# Communications_Module.net
KiCad netlist of a schematic drawn in Altium Designer
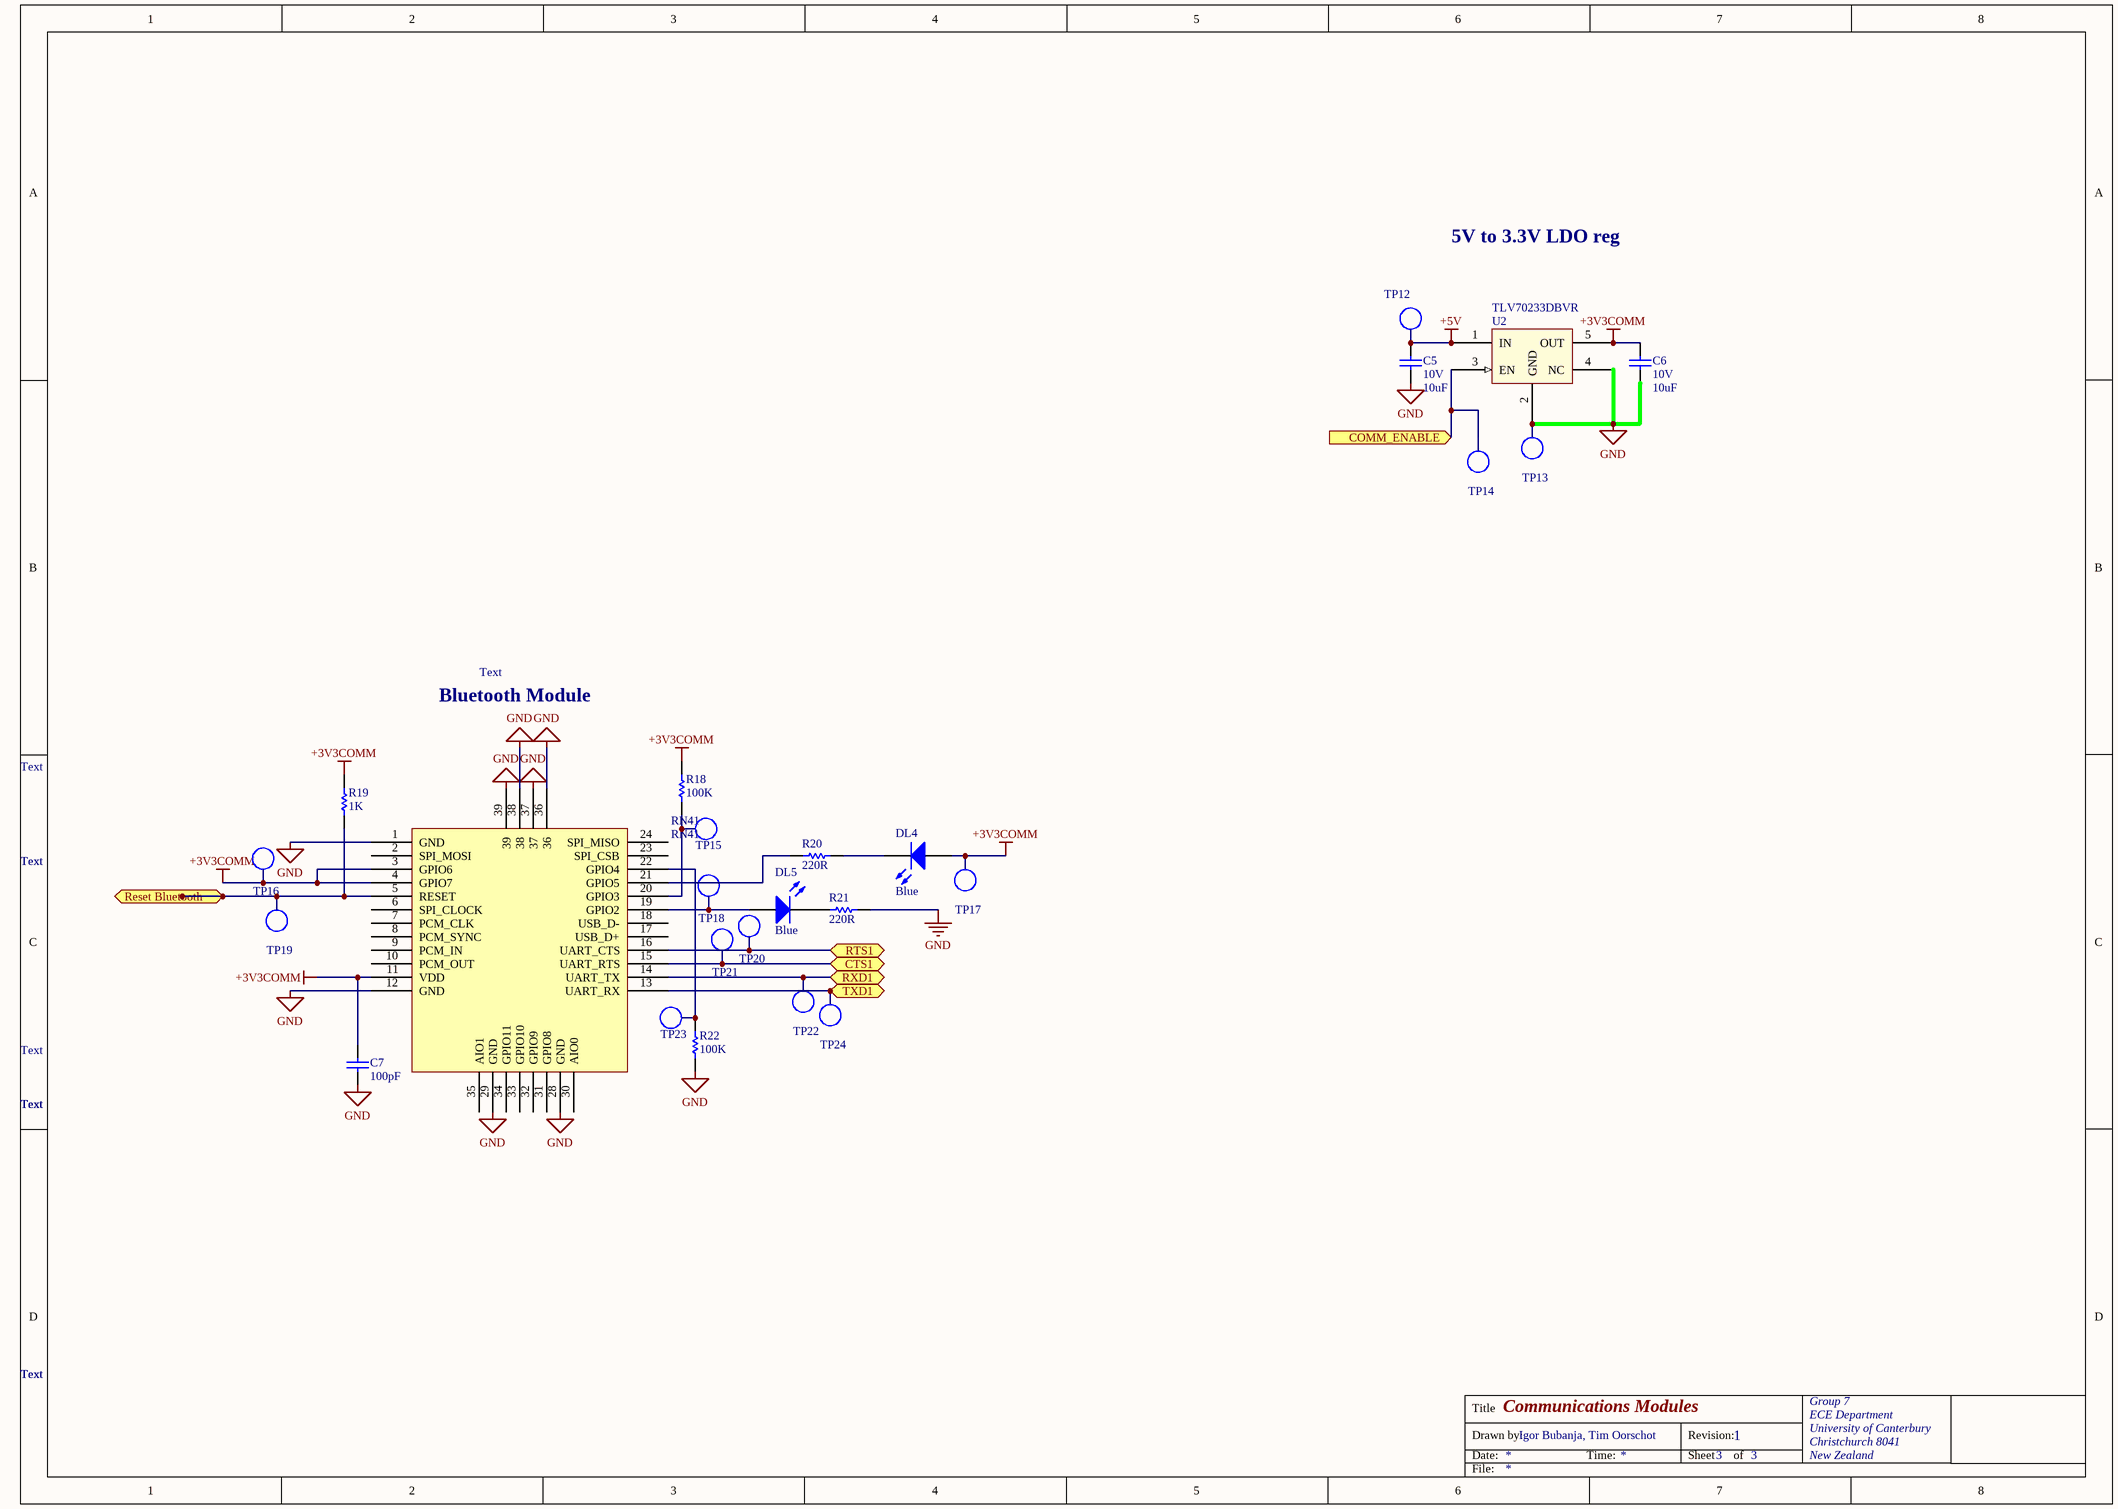
[diagram p0: Communications_Module.SchDoc]

(export (version "E")
  (design (tool "Eeschema 10.0.6"))
  (components
    (comp (ref "C5")
      (value "10uF")
      (footprint "CAPC1608L")
      (description "CAP CER 10UF X5R +-20% 10V 0603")
      (fields (field (name "VOLTAGE - RATED") "10V"))
      (libsource (lib "ECE Components_15_7") (part "CC_10uF_0603"))
    )
    (comp (ref "C6")
      (value "10uF")
      (footprint "CAPC1608L")
      (description "CAP CER 10UF X5R +-20% 10V 0603")
      (fields (field (name "VOLTAGE - RATED") "10V"))
      (libsource (lib "ECE Components_15_7") (part "CC_10uF_0603"))
    )
    (comp (ref "C7")
      (value "100pF")
      (footprint "CAPC1608L")
      (description "CAP CER 100pF NPO/COG +-5% 50V 0603")
      (libsource (lib "ECE Components_15_8") (part "CC_100pF_0603"))
    )
    (comp (ref "DL4")
      (value "Blue")
      (footprint "WL-SMCW0603")
      (description "LED Blue 270mcd 0603 SMD")
      (fields
        (field (name "MANUFACTURER") "WURTH ELEKTRONIK")
        (field (name "MANUFACTURER PART NUMBER") "150060BS75000")
        (field (name "LED COLOUR") "Blue")
      )
      (libsource (lib "ECE Components_15_8") (part "DL_150060BS75000"))
    )
    (comp (ref "DL5")
      (value "Blue")
      (footprint "WL-SMCW0603")
      (description "LED Blue 270mcd 0603 SMD")
      (fields
        (field (name "MANUFACTURER") "WURTH ELEKTRONIK")
        (field (name "MANUFACTURER PART NUMBER") "150060BS75000")
        (field (name "LED COLOUR") "Blue")
      )
      (libsource (lib "ECE Components_15_8") (part "DL_150060BS75000"))
    )
    (comp (ref "R18")
      (value "100K")
      (footprint "RESC1608L")
      (description "RES 100K OHM 1/10W 5% 0603 SMD")
      (libsource (lib "ECE Components_15_8") (part "RS_100K"))
    )
    (comp (ref "R19")
      (value "1K")
      (footprint "RESC1608L")
      (description "RES 1.0K OHM 1/10W 5% 0603 SMD")
      (libsource (lib "ECE Components_15_8") (part "RS_1K"))
    )
    (comp (ref "R20")
      (value "220R")
      (footprint "RESC1608L")
      (description "RES 220 OHM 1/10W 5% 0603 SMD")
      (libsource (lib "ECE Components_15_8") (part "RS_220R"))
    )
    (comp (ref "R21")
      (value "220R")
      (footprint "RESC1608L")
      (description "RES 220 OHM 1/10W 5% 0603 SMD")
      (libsource (lib "ECE Components_15_8") (part "RS_220R"))
    )
    (comp (ref "R22")
      (value "100K")
      (footprint "RESC1608L")
      (description "RES 100K OHM 1/10W 5% 0603 SMD")
      (libsource (lib "ECE Components_15_8") (part "RS_100K"))
    )
    (comp (ref "RN41")
      (value "RN41")
      (footprint "PCBComponent_1")
      (description "Bluetooth RN41")
      (libsource (lib "Schlib2") (part "RN41"))
    )
    (comp (ref "TP12")
      (value "V_Bus")
      (footprint "TP_0805")
      (description "Test Point 2.0X0.9X1.2mm SMD")
      (fields
        (field (name "MANUFACTURER") "TE Connectivity AMP Connectors")
        (field (name "MANUFACTURER PART NUMBER") "1625854-2")
      )
      (libsource (lib "ECE Components_15_7") (part "TP_0805"))
    )
    (comp (ref "TP13")
      (value "Gnd")
      (footprint "TP_0805")
      (description "Test Point 2.0X0.9X1.2mm SMD")
      (fields
        (field (name "MANUFACTURER") "TE Connectivity AMP Connectors")
        (field (name "MANUFACTURER PART NUMBER") "1625854-2")
      )
      (libsource (lib "ECE Components_15_7") (part "TP_0805"))
    )
    (comp (ref "TP14")
      (value "Gnd")
      (footprint "TP_0805")
      (description "Test Point 2.0X0.9X1.2mm SMD")
      (fields
        (field (name "MANUFACTURER") "TE Connectivity AMP Connectors")
        (field (name "MANUFACTURER PART NUMBER") "1625854-2")
      )
      (libsource (lib "ECE Components_15_7") (part "TP_0805"))
    )
    (comp (ref "TP15")
      (value "Gnd")
      (footprint "TP_0805")
      (description "Test Point 2.0X0.9X1.2mm SMD")
      (fields
        (field (name "MANUFACTURER") "TE Connectivity AMP Connectors")
        (field (name "MANUFACTURER PART NUMBER") "1625854-2")
      )
      (libsource (lib "ECE Components_15_7") (part "TP_0805"))
    )
    (comp (ref "TP16")
      (value "Gnd")
      (footprint "TP_0805")
      (description "Test Point 2.0X0.9X1.2mm SMD")
      (fields
        (field (name "MANUFACTURER") "TE Connectivity AMP Connectors")
        (field (name "MANUFACTURER PART NUMBER") "1625854-2")
      )
      (libsource (lib "ECE Components_15_7") (part "TP_0805"))
    )
    (comp (ref "TP17")
      (value "Gnd")
      (footprint "TP_0805")
      (description "Test Point 2.0X0.9X1.2mm SMD")
      (fields
        (field (name "MANUFACTURER") "TE Connectivity AMP Connectors")
        (field (name "MANUFACTURER PART NUMBER") "1625854-2")
      )
      (libsource (lib "ECE Components_15_7") (part "TP_0805"))
    )
    (comp (ref "TP18")
      (value "Gnd")
      (footprint "TP_0805")
      (description "Test Point 2.0X0.9X1.2mm SMD")
      (fields
        (field (name "MANUFACTURER") "TE Connectivity AMP Connectors")
        (field (name "MANUFACTURER PART NUMBER") "1625854-2")
      )
      (libsource (lib "ECE Components_15_7") (part "TP_0805"))
    )
    (comp (ref "TP19")
      (value "Gnd")
      (footprint "TP_0805")
      (description "Test Point 2.0X0.9X1.2mm SMD")
      (fields
        (field (name "MANUFACTURER") "TE Connectivity AMP Connectors")
        (field (name "MANUFACTURER PART NUMBER") "1625854-2")
      )
      (libsource (lib "ECE Components_15_7") (part "TP_0805"))
    )
    (comp (ref "TP20")
      (value "Gnd")
      (footprint "TP_0805")
      (description "Test Point 2.0X0.9X1.2mm SMD")
      (fields
        (field (name "MANUFACTURER") "TE Connectivity AMP Connectors")
        (field (name "MANUFACTURER PART NUMBER") "1625854-2")
      )
      (libsource (lib "ECE Components_15_7") (part "TP_0805"))
    )
    (comp (ref "TP21")
      (value "Gnd")
      (footprint "TP_0805")
      (description "Test Point 2.0X0.9X1.2mm SMD")
      (fields
        (field (name "MANUFACTURER") "TE Connectivity AMP Connectors")
        (field (name "MANUFACTURER PART NUMBER") "1625854-2")
      )
      (libsource (lib "ECE Components_15_7") (part "TP_0805"))
    )
    (comp (ref "TP22")
      (value "Gnd")
      (footprint "TP_0805")
      (description "Test Point 2.0X0.9X1.2mm SMD")
      (fields
        (field (name "MANUFACTURER") "TE Connectivity AMP Connectors")
        (field (name "MANUFACTURER PART NUMBER") "1625854-2")
      )
      (libsource (lib "ECE Components_15_7") (part "TP_0805"))
    )
    (comp (ref "TP23")
      (value "Gnd")
      (footprint "TP_0805")
      (description "Test Point 2.0X0.9X1.2mm SMD")
      (fields
        (field (name "MANUFACTURER") "TE Connectivity AMP Connectors")
        (field (name "MANUFACTURER PART NUMBER") "1625854-2")
      )
      (libsource (lib "ECE Components_15_7") (part "TP_0805"))
    )
    (comp (ref "TP24")
      (value "Gnd")
      (footprint "TP_0805")
      (description "Test Point 2.0X0.9X1.2mm SMD")
      (fields
        (field (name "MANUFACTURER") "TE Connectivity AMP Connectors")
        (field (name "MANUFACTURER PART NUMBER") "1625854-2")
      )
      (libsource (lib "ECE Components_15_7") (part "TP_0805"))
    )
    (comp (ref "U2")
      (value "TLV70233DBVR")
      (footprint "SOT95P280X145-5N")
      (description "IC REG LDO 3.3V 0.3A SOT23-5")
      (fields
        (field (name "MANUFACTURER") "Texas Instruments")
        (field (name "MANUFACTURER PART NUMBER") "TLV70233DBVR")
      )
      (libsource (lib "ECE Components_15_7") (part "SV_TLV70233DBVR"))
    )
  )
  (nets
    (net (code "1") (name "+3V3COMM") (class "Default")
      (node (ref "C6") (pin "1") (pinfunction "1_1") (pintype "passive"))
      (node (ref "C7") (pin "2") (pinfunction "2_2") (pintype "passive"))
      (node (ref "DL4") (pin "2") (pinfunction "A_2") (pintype "passive"))
      (node (ref "R18") (pin "2") (pinfunction "2_2") (pintype "passive"))
      (node (ref "R19") (pin "2") (pinfunction "2_2") (pintype "passive"))
      (node (ref "RN41") (pin "11") (pinfunction "VDD_11") (pintype "power_in"))
      (node (ref "RN41") (pin "3") (pinfunction "GPIO6_3") (pintype "passive"))
      (node (ref "RN41") (pin "4") (pinfunction "GPIO7_4") (pintype "passive"))
      (node (ref "TP16") (pin "1") (pinfunction "TP_1") (pintype "passive"))
      (node (ref "TP17") (pin "1") (pinfunction "TP_1") (pintype "passive"))
      (node (ref "U2") (pin "5") (pinfunction "OUT_5") (pintype "power_in"))
    )
    (net (code "2") (name "+5V") (class "Default")
      (node (ref "C5") (pin "1") (pinfunction "1_1") (pintype "passive"))
      (node (ref "TP12") (pin "1") (pinfunction "TP_1") (pintype "passive"))
      (node (ref "U2") (pin "1") (pinfunction "IN_1") (pintype "power_in"))
    )
    (net (code "3") (name "/COMM_ENABLE") (class "Default")
      (node (ref "TP14") (pin "1") (pinfunction "TP_1") (pintype "passive"))
      (node (ref "U2") (pin "3") (pinfunction "EN_3") (pintype "input"))
    )
    (net (code "4") (name "/CTS1") (class "Default")
      (node (ref "RN41") (pin "15") (pinfunction "UART_RTS_15") (pintype "passive"))
      (node (ref "TP21") (pin "1") (pinfunction "TP_1") (pintype "passive"))
    )
    (net (code "5") (name "/RTS1") (class "Default")
      (node (ref "RN41") (pin "16") (pinfunction "UART_CTS_16") (pintype "passive"))
      (node (ref "TP20") (pin "1") (pinfunction "TP_1") (pintype "passive"))
    )
    (net (code "6") (name "/RXD1") (class "Default")
      (node (ref "RN41") (pin "14") (pinfunction "UART_TX_14") (pintype "passive"))
      (node (ref "TP22") (pin "1") (pinfunction "TP_1") (pintype "passive"))
    )
    (net (code "7") (name "/Reset Bluetooth") (class "Default")
      (node (ref "R19") (pin "1") (pinfunction "1_1") (pintype "passive"))
      (node (ref "RN41") (pin "5") (pinfunction "RESET_5") (pintype "passive"))
      (node (ref "TP19") (pin "1") (pinfunction "TP_1") (pintype "passive"))
    )
    (net (code "8") (name "/TXD1") (class "Default")
      (node (ref "RN41") (pin "13") (pinfunction "UART_RX_13") (pintype "passive"))
      (node (ref "TP24") (pin "1") (pinfunction "TP_1") (pintype "passive"))
    )
    (net (code "9") (name "GND") (class "Default")
      (node (ref "C5") (pin "2") (pinfunction "2_2") (pintype "passive"))
      (node (ref "C6") (pin "2") (pinfunction "2_2") (pintype "passive"))
      (node (ref "C7") (pin "1") (pinfunction "1_1") (pintype "passive"))
      (node (ref "R21") (pin "2") (pinfunction "2_2") (pintype "passive"))
      (node (ref "R22") (pin "1") (pinfunction "1_1") (pintype "passive"))
      (node (ref "RN41") (pin "1") (pinfunction "GND_1") (pintype "power_in"))
      (node (ref "RN41") (pin "12") (pinfunction "GND_12") (pintype "power_in"))
      (node (ref "RN41") (pin "28") (pinfunction "GND_28") (pintype "power_in"))
      (node (ref "RN41") (pin "29") (pinfunction "GND_29") (pintype "power_in"))
      (node (ref "RN41") (pin "36") (pinfunction "36_36") (pintype "passive"))
      (node (ref "RN41") (pin "37") (pinfunction "37_37") (pintype "passive"))
      (node (ref "RN41") (pin "38") (pinfunction "38_38") (pintype "passive"))
      (node (ref "RN41") (pin "39") (pinfunction "39_39") (pintype "passive"))
      (node (ref "TP13") (pin "1") (pinfunction "TP_1") (pintype "passive"))
      (node (ref "U2") (pin "2") (pinfunction "GND_2") (pintype "power_in"))
      (node (ref "U2") (pin "4") (pinfunction "NC_4") (pintype "passive"))
    )
    (net (code "10") (name "Net-(DL4-K)") (class "Default")
      (node (ref "DL4") (pin "1") (pinfunction "K_1") (pintype "passive"))
      (node (ref "R20") (pin "2") (pinfunction "2_2") (pintype "passive"))
    )
    (net (code "11") (name "Net-(DL5-A)") (class "Default")
      (node (ref "DL5") (pin "2") (pinfunction "A_2") (pintype "passive"))
      (node (ref "RN41") (pin "19") (pinfunction "GPIO2_19") (pintype "passive"))
      (node (ref "TP18") (pin "1") (pinfunction "TP_1") (pintype "passive"))
    )
    (net (code "12") (name "Net-(DL5-K)") (class "Default")
      (node (ref "DL5") (pin "1") (pinfunction "K_1") (pintype "passive"))
      (node (ref "R21") (pin "1") (pinfunction "1_1") (pintype "passive"))
    )
    (net (code "13") (name "Net-(RN41-GPIO3)") (class "Default")
      (node (ref "R18") (pin "1") (pinfunction "1_1") (pintype "passive"))
      (node (ref "RN41") (pin "20") (pinfunction "GPIO3_20") (pintype "passive"))
      (node (ref "TP15") (pin "1") (pinfunction "TP_1") (pintype "passive"))
    )
    (net (code "14") (name "Net-(RN41-GPIO4)") (class "Default")
      (node (ref "R22") (pin "2") (pinfunction "2_2") (pintype "passive"))
      (node (ref "RN41") (pin "22") (pinfunction "GPIO4_22") (pintype "passive"))
      (node (ref "TP23") (pin "1") (pinfunction "TP_1") (pintype "passive"))
    )
    (net (code "15") (name "Net-(RN41-GPIO5)") (class "Default")
      (node (ref "R20") (pin "1") (pinfunction "1_1") (pintype "passive"))
      (node (ref "RN41") (pin "21") (pinfunction "GPIO5_21") (pintype "passive"))
    )
    (net (code "16") (name "unconnected-(RN41-AIO0-Pad30)") (class "Default")
      (node (ref "RN41") (pin "30") (pinfunction "AIO0_30") (pintype "passive"))
    )
    (net (code "17") (name "unconnected-(RN41-AIO1-Pad35)") (class "Default")
      (node (ref "RN41") (pin "35") (pinfunction "AIO1_35") (pintype "passive"))
    )
    (net (code "18") (name "unconnected-(RN41-GPIO8-Pad31)") (class "Default")
      (node (ref "RN41") (pin "31") (pinfunction "GPIO8_31") (pintype "passive"))
    )
    (net (code "19") (name "unconnected-(RN41-GPIO9-Pad32)") (class "Default")
      (node (ref "RN41") (pin "32") (pinfunction "GPIO9_32") (pintype "passive"))
    )
    (net (code "20") (name "unconnected-(RN41-GPIO10-Pad33)") (class "Default")
      (node (ref "RN41") (pin "33") (pinfunction "GPIO10_33") (pintype "passive"))
    )
    (net (code "21") (name "unconnected-(RN41-GPIO11-Pad34)") (class "Default")
      (node (ref "RN41") (pin "34") (pinfunction "GPIO11_34") (pintype "passive"))
    )
    (net (code "22") (name "unconnected-(RN41-PCM_CLK-Pad7)") (class "Default")
      (node (ref "RN41") (pin "7") (pinfunction "PCM_CLK_7") (pintype "passive"))
    )
    (net (code "23") (name "unconnected-(RN41-PCM_IN-Pad9)") (class "Default")
      (node (ref "RN41") (pin "9") (pinfunction "PCM_IN_9") (pintype "passive"))
    )
    (net (code "24") (name "unconnected-(RN41-PCM_OUT-Pad10)") (class "Default")
      (node (ref "RN41") (pin "10") (pinfunction "PCM_OUT_10") (pintype "passive"))
    )
    (net (code "25") (name "unconnected-(RN41-PCM_SYNC-Pad8)") (class "Default")
      (node (ref "RN41") (pin "8") (pinfunction "PCM_SYNC_8") (pintype "passive"))
    )
    (net (code "26") (name "unconnected-(RN41-SPI_CLOCK-Pad6)") (class "Default")
      (node (ref "RN41") (pin "6") (pinfunction "SPI_CLOCK_6") (pintype "passive"))
    )
    (net (code "27") (name "unconnected-(RN41-SPI_CSB-Pad23)") (class "Default")
      (node (ref "RN41") (pin "23") (pinfunction "SPI_CSB_23") (pintype "passive"))
    )
    (net (code "28") (name "unconnected-(RN41-SPI_MISO-Pad24)") (class "Default")
      (node (ref "RN41") (pin "24") (pinfunction "SPI_MISO_24") (pintype "passive"))
    )
    (net (code "29") (name "unconnected-(RN41-SPI_MOSI-Pad2)") (class "Default")
      (node (ref "RN41") (pin "2") (pinfunction "SPI_MOSI_2") (pintype "passive"))
    )
    (net (code "30") (name "unconnected-(RN41-USB_D+-Pad17)") (class "Default")
      (node (ref "RN41") (pin "17") (pinfunction "USB_D+_17") (pintype "passive"))
    )
    (net (code "31") (name "unconnected-(RN41-USB_D--Pad18)") (class "Default")
      (node (ref "RN41") (pin "18") (pinfunction "USB_D-_18") (pintype "passive"))
    )
  )
)
